# smars_sch.net
KiCad netlist of a schematic drawn in Altium Designer
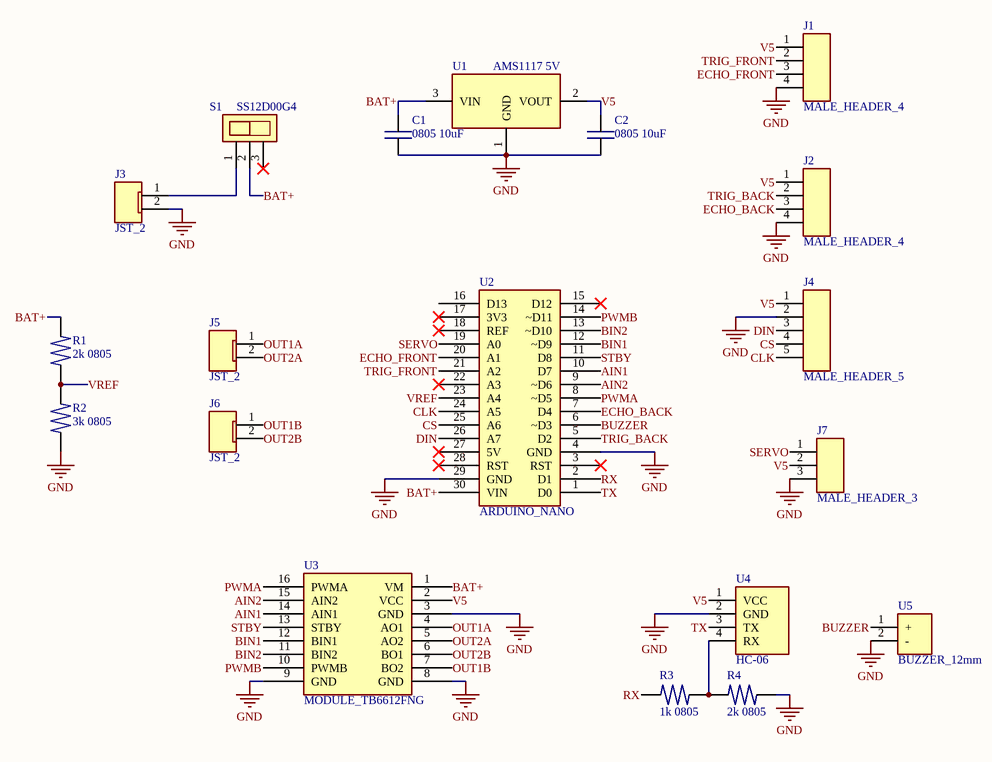
[diagram p0: smars_sch.SchDoc]

(export (version "E")
  (design (tool "Eeschema 10.0.6"))
  (components
    (comp (ref "C1")
      (value "0805 10uF")
      (footprint "CAPACITOR 0805")
      (description "Generic Capacitor 0805, 2x1.25x1.4mm.")
      (libsource (lib "Ceramic Capacitor") (part "CAPACITOR 0805"))
    )
    (comp (ref "C2")
      (value "0805 10uF")
      (footprint "CAPACITOR 0805")
      (description "Generic Capacitor 0805, 2x1.25x1.4mm.")
      (libsource (lib "Ceramic Capacitor") (part "CAPACITOR 0805"))
    )
    (comp (ref "J1")
      (value "MALE_HEADER_4")
      (footprint "MALE_4")
      (description "Male Header Connector 2.54mm 4 Pins.")
      (libsource (lib "Connectors") (part "MALE_HEADER_4"))
    )
    (comp (ref "J2")
      (value "MALE_HEADER_4")
      (footprint "MALE_4")
      (description "Male Header Connector 2.54mm 4 Pins.")
      (libsource (lib "Connectors") (part "MALE_HEADER_4"))
    )
    (comp (ref "J3")
      (value "JST_2")
      (footprint "JST_2")
      (description "Female Connector JST 2 Vias, 2.54mm.")
      (libsource (lib "Connectors") (part "JST_2"))
    )
    (comp (ref "J4")
      (value "MALE_HEADER_5")
      (footprint "MALE_5")
      (description "Male Header Connector 2.54mm 5 Pins.")
      (libsource (lib "Connectors") (part "MALE_HEADER_5"))
    )
    (comp (ref "J5")
      (value "JST_2")
      (footprint "JST_2")
      (description "Female Connector JST 2 Vias, 2.54mm.")
      (libsource (lib "Connectors") (part "JST_2"))
    )
    (comp (ref "J6")
      (value "JST_2")
      (footprint "JST_2")
      (description "Female Connector JST 2 Vias, 2.54mm.")
      (libsource (lib "Connectors") (part "JST_2"))
    )
    (comp (ref "J7")
      (value "MALE_HEADER_3")
      (footprint "MALE_3")
      (description "Male Header Connector 2.54mm 3 Pins.")
      (libsource (lib "Connectors") (part "MALE_HEADER_3"))
    )
    (comp (ref "R1")
      (value "2k 0805")
      (footprint "RESISTOR_0805")
      (description "Generic Resistor 0805.")
      (libsource (lib "Resistors") (part "RESISTOR_0805"))
    )
    (comp (ref "R2")
      (value "3k 0805")
      (footprint "RESISTOR_0805")
      (description "Generic Resistor 0805.")
      (libsource (lib "Resistors") (part "RESISTOR_0805"))
    )
    (comp (ref "R3")
      (value "1k 0805")
      (footprint "RESISTOR_0805")
      (description "Generic Resistor 0805.")
      (libsource (lib "Resistors") (part "RESISTOR_0805"))
    )
    (comp (ref "R4")
      (value "2k 0805")
      (footprint "RESISTOR_0805")
      (description "Generic Resistor 0805.")
      (libsource (lib "Resistors") (part "RESISTOR_0805"))
    )
    (comp (ref "S1")
      (value "SS12D00G4")
      (footprint "SS12D00G4")
      (description "Vertical Slide Switch 3 Pins.")
      (libsource (lib "Buttons & Switches") (part "SS12D00G4"))
    )
    (comp (ref "U1")
      (value "AMS1117 5V")
      (footprint "AMS1117")
      (description "IC REG LINEAR 1A SOT-89-3L")
      (libsource (lib "Voltage Regulators") (part "AMS1117"))
    )
    (comp (ref "U2")
      (value "ARDUINO_NANO")
      (footprint "ARDUINO_NANO")
      (description "Based on ATmega328P, Clock 16MHz, Flash 32KB, 14 Digital Pins, 8 Analog Pins, 5V, Vin 7-12V.")
      (libsource (lib "Arduino") (part "ARDUINO_NANO"))
    )
    (comp (ref "U3")
      (value "MODULE_TB6612FNG")
      (footprint "MODULE_TB6612FNG")
      (description "Module Dual Motor Driver 2.5-13.5V 3.2A Peak 21x18mm")
      (libsource (lib "Motor Drivers") (part "MODULE_TB6612FNG"))
    )
    (comp (ref "U4")
      (value "HC-06")
      (footprint "HC-06")
      (description "BLUETOOTH MODULE, 4 Pins.")
      (libsource (lib "Communication") (part "HC-06"))
    )
    (comp (ref "U5")
      (value "BUZZER_12mm")
      (footprint "BUZZER_12mm")
      (description "BUZZER MAGNETIC 12MM")
      (libsource (lib "Random") (part "BUZZER_12mm"))
    )
  )
  (nets
    (net (code "1") (name "/AIN1") (class "Default")
      (node (ref "U2") (pin "10") (pinfunction "D7_10") (pintype "passive"))
      (node (ref "U3") (pin "14") (pinfunction "AIN1_14") (pintype "passive"))
    )
    (net (code "2") (name "/AIN2") (class "Default")
      (node (ref "U2") (pin "9") (pinfunction "~D6_9") (pintype "passive"))
      (node (ref "U3") (pin "15") (pinfunction "AIN2_15") (pintype "passive"))
    )
    (net (code "3") (name "/BAT+") (class "Default")
      (node (ref "C1") (pin "2") (pinfunction "2_2") (pintype "passive"))
      (node (ref "R1") (pin "2") (pinfunction "2_2") (pintype "passive"))
      (node (ref "S1") (pin "2") (pintype "passive"))
      (node (ref "U1") (pin "3") (pinfunction "VIN_3") (pintype "passive"))
      (node (ref "U2") (pin "30") (pinfunction "VIN_30") (pintype "passive"))
      (node (ref "U3") (pin "1") (pinfunction "VM_1") (pintype "passive"))
    )
    (net (code "4") (name "/BIN1") (class "Default")
      (node (ref "U2") (pin "12") (pinfunction "~D9_12") (pintype "passive"))
      (node (ref "U3") (pin "12") (pinfunction "BIN1_12") (pintype "passive"))
    )
    (net (code "5") (name "/BIN2") (class "Default")
      (node (ref "U2") (pin "13") (pinfunction "~D10_13") (pintype "passive"))
      (node (ref "U3") (pin "11") (pinfunction "BIN2_11") (pintype "passive"))
    )
    (net (code "6") (name "/BUZZER") (class "Default")
      (node (ref "U2") (pin "6") (pinfunction "~D3_6") (pintype "passive"))
      (node (ref "U5") (pin "1") (pinfunction "+_1") (pintype "passive"))
    )
    (net (code "7") (name "/CLK") (class "Default")
      (node (ref "J4") (pin "5") (pintype "passive"))
      (node (ref "U2") (pin "24") (pinfunction "A5_24") (pintype "passive"))
    )
    (net (code "8") (name "/CS") (class "Default")
      (node (ref "J4") (pin "4") (pintype "passive"))
      (node (ref "U2") (pin "25") (pinfunction "A6_25") (pintype "passive"))
    )
    (net (code "9") (name "/DIN") (class "Default")
      (node (ref "J4") (pin "3") (pintype "passive"))
      (node (ref "U2") (pin "26") (pinfunction "A7_26") (pintype "passive"))
    )
    (net (code "10") (name "/ECHO_BACK") (class "Default")
      (node (ref "J2") (pin "3") (pintype "passive"))
      (node (ref "U2") (pin "7") (pinfunction "D4_7") (pintype "passive"))
    )
    (net (code "11") (name "/ECHO_FRONT") (class "Default")
      (node (ref "J1") (pin "3") (pintype "passive"))
      (node (ref "U2") (pin "20") (pinfunction "A1_20") (pintype "passive"))
    )
    (net (code "12") (name "/OUT1A") (class "Default")
      (node (ref "J5") (pin "1") (pintype "passive"))
      (node (ref "U3") (pin "4") (pinfunction "AO1_4") (pintype "passive"))
    )
    (net (code "13") (name "/OUT1B") (class "Default")
      (node (ref "J6") (pin "1") (pintype "passive"))
      (node (ref "U3") (pin "7") (pinfunction "BO2_7") (pintype "passive"))
    )
    (net (code "14") (name "/OUT2A") (class "Default")
      (node (ref "J5") (pin "2") (pintype "passive"))
      (node (ref "U3") (pin "5") (pinfunction "AO2_5") (pintype "passive"))
    )
    (net (code "15") (name "/OUT2B") (class "Default")
      (node (ref "J6") (pin "2") (pintype "passive"))
      (node (ref "U3") (pin "6") (pinfunction "BO1_6") (pintype "passive"))
    )
    (net (code "16") (name "/PWMA") (class "Default")
      (node (ref "U2") (pin "8") (pinfunction "~D5_8") (pintype "passive"))
      (node (ref "U3") (pin "16") (pinfunction "PWMA_16") (pintype "passive"))
    )
    (net (code "17") (name "/PWMB") (class "Default")
      (node (ref "U2") (pin "14") (pinfunction "~D11_14") (pintype "passive"))
      (node (ref "U3") (pin "10") (pinfunction "PWMB_10") (pintype "passive"))
    )
    (net (code "18") (name "/RX") (class "Default")
      (node (ref "R3") (pin "1") (pinfunction "1_1") (pintype "passive"))
      (node (ref "U2") (pin "2") (pinfunction "D1_2") (pintype "passive"))
    )
    (net (code "19") (name "/SERVO") (class "Default")
      (node (ref "J7") (pin "1") (pintype "passive"))
      (node (ref "U2") (pin "19") (pinfunction "A0_19") (pintype "passive"))
    )
    (net (code "20") (name "/STBY") (class "Default")
      (node (ref "U2") (pin "11") (pinfunction "D8_11") (pintype "passive"))
      (node (ref "U3") (pin "13") (pinfunction "STBY_13") (pintype "passive"))
    )
    (net (code "21") (name "/TRIG_BACK") (class "Default")
      (node (ref "J2") (pin "2") (pintype "passive"))
      (node (ref "U2") (pin "5") (pinfunction "D2_5") (pintype "passive"))
    )
    (net (code "22") (name "/TRIG_FRONT") (class "Default")
      (node (ref "J1") (pin "2") (pintype "passive"))
      (node (ref "U2") (pin "21") (pinfunction "A2_21") (pintype "passive"))
    )
    (net (code "23") (name "/TX") (class "Default")
      (node (ref "U2") (pin "1") (pinfunction "D0_1") (pintype "passive"))
      (node (ref "U4") (pin "3") (pinfunction "TX_3") (pintype "passive"))
    )
    (net (code "24") (name "/V5") (class "Default")
      (node (ref "C2") (pin "2") (pinfunction "2_2") (pintype "passive"))
      (node (ref "J1") (pin "1") (pintype "passive"))
      (node (ref "J2") (pin "1") (pintype "passive"))
      (node (ref "J4") (pin "1") (pintype "passive"))
      (node (ref "J7") (pin "2") (pintype "passive"))
      (node (ref "U1") (pin "2") (pinfunction "VOUT_2") (pintype "passive"))
      (node (ref "U3") (pin "2") (pinfunction "VCC_2") (pintype "passive"))
      (node (ref "U4") (pin "1") (pinfunction "VCC_1") (pintype "passive"))
    )
    (net (code "25") (name "/VREF") (class "Default")
      (node (ref "R1") (pin "1") (pinfunction "1_1") (pintype "passive"))
      (node (ref "R2") (pin "1") (pinfunction "1_1") (pintype "passive"))
      (node (ref "U2") (pin "23") (pinfunction "A4_23") (pintype "passive"))
    )
    (net (code "26") (name "GND") (class "Default")
      (node (ref "C1") (pin "1") (pinfunction "1_1") (pintype "passive"))
      (node (ref "C2") (pin "1") (pinfunction "1_1") (pintype "passive"))
      (node (ref "J1") (pin "4") (pintype "passive"))
      (node (ref "J2") (pin "4") (pintype "passive"))
      (node (ref "J3") (pin "2") (pintype "passive"))
      (node (ref "J4") (pin "2") (pintype "passive"))
      (node (ref "J7") (pin "3") (pintype "passive"))
      (node (ref "R2") (pin "2") (pinfunction "2_2") (pintype "passive"))
      (node (ref "R4") (pin "1") (pinfunction "1_1") (pintype "passive"))
      (node (ref "U1") (pin "1") (pinfunction "GND_1") (pintype "passive"))
      (node (ref "U2") (pin "29") (pinfunction "GND_29") (pintype "passive"))
      (node (ref "U2") (pin "4") (pinfunction "GND_4") (pintype "passive"))
      (node (ref "U3") (pin "3") (pinfunction "GND_3") (pintype "passive"))
      (node (ref "U3") (pin "8") (pinfunction "GND_8") (pintype "passive"))
      (node (ref "U3") (pin "9") (pinfunction "GND_9") (pintype "passive"))
      (node (ref "U4") (pin "2") (pinfunction "GND_2") (pintype "passive"))
      (node (ref "U5") (pin "2") (pinfunction "-_2") (pintype "passive"))
    )
    (net (code "27") (name "Net-(J3-Pad1)") (class "Default")
      (node (ref "J3") (pin "1") (pintype "passive"))
      (node (ref "S1") (pin "1") (pintype "passive"))
    )
    (net (code "28") (name "Net-(U4-RX)") (class "Default")
      (node (ref "R3") (pin "2") (pinfunction "2_2") (pintype "passive"))
      (node (ref "R4") (pin "2") (pinfunction "2_2") (pintype "passive"))
      (node (ref "U4") (pin "4") (pinfunction "RX_4") (pintype "passive"))
    )
    (net (code "29") (name "unconnected-(S1-Pad3)") (class "Default")
      (node (ref "S1") (pin "3") (pintype "passive+no_connect"))
    )
    (net (code "30") (name "unconnected-(U2-3V3-Pad17)") (class "Default")
      (node (ref "U2") (pin "17") (pinfunction "3V3_17") (pintype "passive+no_connect"))
    )
    (net (code "31") (name "unconnected-(U2-5V-Pad27)") (class "Default")
      (node (ref "U2") (pin "27") (pinfunction "5V_27") (pintype "passive+no_connect"))
    )
    (net (code "32") (name "unconnected-(U2-A3-Pad22)") (class "Default")
      (node (ref "U2") (pin "22") (pinfunction "A3_22") (pintype "passive+no_connect"))
    )
    (net (code "33") (name "unconnected-(U2-D12-Pad15)") (class "Default")
      (node (ref "U2") (pin "15") (pinfunction "D12_15") (pintype "passive+no_connect"))
    )
    (net (code "34") (name "unconnected-(U2-D13-Pad16)") (class "Default")
      (node (ref "U2") (pin "16") (pinfunction "D13_16") (pintype "passive"))
    )
    (net (code "35") (name "unconnected-(U2-REF-Pad18)") (class "Default")
      (node (ref "U2") (pin "18") (pinfunction "REF_18") (pintype "passive+no_connect"))
    )
    (net (code "36") (name "unconnected-(U2-RST-Pad3)") (class "Default")
      (node (ref "U2") (pin "3") (pinfunction "RST_3") (pintype "passive+no_connect"))
    )
    (net (code "37") (name "unconnected-(U2-RST-Pad28)") (class "Default")
      (node (ref "U2") (pin "28") (pinfunction "RST_28") (pintype "passive+no_connect"))
    )
  )
)
